# PWM.net
KiCad netlist of a schematic drawn in Altium Designer
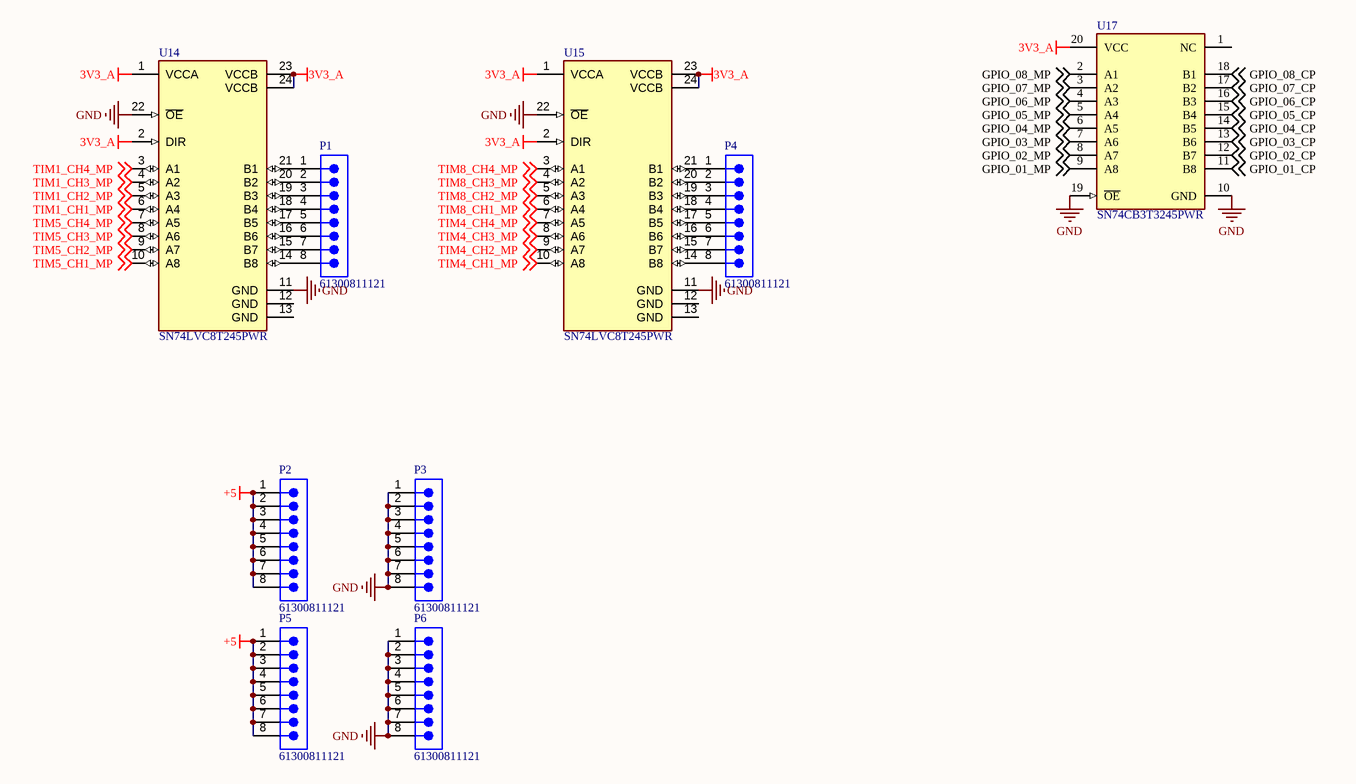
[diagram p0: PWM.SchDoc]

(export (version "E")
  (design (tool "Eeschema 10.0.6"))
  (components
    (comp (ref "P1")
      (value "61300811121")
      (footprint "61300811121")
      (libsource (lib "Altium Content Vault") (part "Header_Male_1R_08P"))
    )
    (comp (ref "P2")
      (value "61300811121")
      (footprint "61300811121")
      (libsource (lib "Altium Content Vault") (part "Header_Male_1R_08P"))
    )
    (comp (ref "P3")
      (value "61300811121")
      (footprint "61300811121")
      (libsource (lib "Altium Content Vault") (part "Header_Male_1R_08P"))
    )
    (comp (ref "P4")
      (value "61300811121")
      (footprint "61300811121")
      (libsource (lib "Altium Content Vault") (part "Header_Male_1R_08P"))
    )
    (comp (ref "P5")
      (value "61300811121")
      (footprint "61300811121")
      (libsource (lib "Altium Content Vault") (part "Header_Male_1R_08P"))
    )
    (comp (ref "P6")
      (value "61300811121")
      (footprint "61300811121")
      (libsource (lib "Altium Content Vault") (part "Header_Male_1R_08P"))
    )
    (comp (ref "U14")
      (value "SN74LVC8T245PWR")
      (footprint "FP-PW0024A-MFG")
      (description "IC TRNSLTR BIDIRECTIONAL 24TSSOP")
      (fields
        (field (name "OCTOPART") "https://octopart.com/sn74lvc8t245pwr-texas+instruments-517164")
        (field (name "MANUFACTURER") "Texas Instruments")
      )
      (libsource (lib "Altium Content Vault") (part "51221a7e4c45eff2cf920f7ccaf63e0"))
    )
    (comp (ref "U15")
      (value "SN74LVC8T245PWR")
      (footprint "FP-PW0024A-MFG")
      (description "IC TRNSLTR BIDIRECTIONAL 24TSSOP")
      (fields
        (field (name "OCTOPART") "https://octopart.com/sn74lvc8t245pwr-texas+instruments-517164")
        (field (name "MANUFACTURER") "Texas Instruments")
      )
      (libsource (lib "Altium Content Vault") (part "51221a7e4c45eff2cf920f7ccaf63e0"))
    )
    (comp (ref "U17")
      (value "SN74CB3T3245PWR")
      (footprint "FP-PW0020A-MFG")
      (description "IC 2.5/3.3V FET BUS SW 20-TSSOP")
      (libsource (lib "Altium Content Vault") (part "98be695b3fbfc448da199ccefa430d5"))
    )
  )
  (nets
    (net (code "1") (name "+5") (class "Default")
      (node (ref "P2") (pin "1") (pinfunction "1_1") (pintype "passive"))
      (node (ref "P2") (pin "2") (pinfunction "2_2") (pintype "passive"))
      (node (ref "P2") (pin "3") (pinfunction "3_3") (pintype "passive"))
      (node (ref "P2") (pin "4") (pinfunction "4_4") (pintype "passive"))
      (node (ref "P2") (pin "5") (pinfunction "5_5") (pintype "passive"))
      (node (ref "P2") (pin "6") (pinfunction "6_6") (pintype "passive"))
      (node (ref "P2") (pin "7") (pinfunction "7_7") (pintype "passive"))
      (node (ref "P2") (pin "8") (pinfunction "8_8") (pintype "passive"))
      (node (ref "P5") (pin "1") (pinfunction "1_1") (pintype "passive"))
      (node (ref "P5") (pin "2") (pinfunction "2_2") (pintype "passive"))
      (node (ref "P5") (pin "3") (pinfunction "3_3") (pintype "passive"))
      (node (ref "P5") (pin "4") (pinfunction "4_4") (pintype "passive"))
      (node (ref "P5") (pin "5") (pinfunction "5_5") (pintype "passive"))
      (node (ref "P5") (pin "6") (pinfunction "6_6") (pintype "passive"))
      (node (ref "P5") (pin "7") (pinfunction "7_7") (pintype "passive"))
      (node (ref "P5") (pin "8") (pinfunction "8_8") (pintype "passive"))
    )
    (net (code "2") (name "3V3_A") (class "Default")
      (node (ref "U14") (pin "1") (pinfunction "VCCA_1") (pintype "power_in"))
      (node (ref "U14") (pin "2") (pinfunction "DIR_2") (pintype "input"))
      (node (ref "U14") (pin "23") (pinfunction "VCCB_23") (pintype "power_in"))
      (node (ref "U14") (pin "24") (pinfunction "VCCB_24") (pintype "power_in"))
      (node (ref "U15") (pin "1") (pinfunction "VCCA_1") (pintype "power_in"))
      (node (ref "U15") (pin "2") (pinfunction "DIR_2") (pintype "input"))
      (node (ref "U15") (pin "23") (pinfunction "VCCB_23") (pintype "power_in"))
      (node (ref "U15") (pin "24") (pinfunction "VCCB_24") (pintype "power_in"))
      (node (ref "U17") (pin "20") (pinfunction "VCC_20") (pintype "power_in"))
    )
    (net (code "3") (name "GND") (class "Default")
      (node (ref "P3") (pin "1") (pinfunction "1_1") (pintype "passive"))
      (node (ref "P3") (pin "2") (pinfunction "2_2") (pintype "passive"))
      (node (ref "P3") (pin "3") (pinfunction "3_3") (pintype "passive"))
      (node (ref "P3") (pin "4") (pinfunction "4_4") (pintype "passive"))
      (node (ref "P3") (pin "5") (pinfunction "5_5") (pintype "passive"))
      (node (ref "P3") (pin "6") (pinfunction "6_6") (pintype "passive"))
      (node (ref "P3") (pin "7") (pinfunction "7_7") (pintype "passive"))
      (node (ref "P3") (pin "8") (pinfunction "8_8") (pintype "passive"))
      (node (ref "P6") (pin "1") (pinfunction "1_1") (pintype "passive"))
      (node (ref "P6") (pin "2") (pinfunction "2_2") (pintype "passive"))
      (node (ref "P6") (pin "3") (pinfunction "3_3") (pintype "passive"))
      (node (ref "P6") (pin "4") (pinfunction "4_4") (pintype "passive"))
      (node (ref "P6") (pin "5") (pinfunction "5_5") (pintype "passive"))
      (node (ref "P6") (pin "6") (pinfunction "6_6") (pintype "passive"))
      (node (ref "P6") (pin "7") (pinfunction "7_7") (pintype "passive"))
      (node (ref "P6") (pin "8") (pinfunction "8_8") (pintype "passive"))
      (node (ref "U14") (pin "11") (pinfunction "GND_11") (pintype "power_in"))
      (node (ref "U14") (pin "22") (pinfunction "~{OE}_22") (pintype "input"))
      (node (ref "U15") (pin "11") (pinfunction "GND_11") (pintype "power_in"))
      (node (ref "U15") (pin "22") (pinfunction "~{OE}_22") (pintype "input"))
      (node (ref "U17") (pin "10") (pinfunction "GND_10") (pintype "power_in"))
      (node (ref "U17") (pin "19") (pinfunction "~{OE}_19") (pintype "input"))
    )
    (net (code "4") (name "GPIO_01_CP") (class "Default")
      (node (ref "U17") (pin "11") (pinfunction "B8_11") (pintype "passive"))
    )
    (net (code "5") (name "GPIO_01_MP") (class "Default")
      (node (ref "U17") (pin "9") (pinfunction "A8_9") (pintype "passive"))
    )
    (net (code "6") (name "GPIO_02_CP") (class "Default")
      (node (ref "U17") (pin "12") (pinfunction "B7_12") (pintype "passive"))
    )
    (net (code "7") (name "GPIO_02_MP") (class "Default")
      (node (ref "U17") (pin "8") (pinfunction "A7_8") (pintype "passive"))
    )
    (net (code "8") (name "GPIO_03_CP") (class "Default")
      (node (ref "U17") (pin "13") (pinfunction "B6_13") (pintype "passive"))
    )
    (net (code "9") (name "GPIO_03_MP") (class "Default")
      (node (ref "U17") (pin "7") (pinfunction "A6_7") (pintype "passive"))
    )
    (net (code "10") (name "GPIO_04_CP") (class "Default")
      (node (ref "U17") (pin "14") (pinfunction "B5_14") (pintype "passive"))
    )
    (net (code "11") (name "GPIO_04_MP") (class "Default")
      (node (ref "U17") (pin "6") (pinfunction "A5_6") (pintype "passive"))
    )
    (net (code "12") (name "GPIO_05_CP") (class "Default")
      (node (ref "U17") (pin "15") (pinfunction "B4_15") (pintype "passive"))
    )
    (net (code "13") (name "GPIO_05_MP") (class "Default")
      (node (ref "U17") (pin "5") (pinfunction "A4_5") (pintype "passive"))
    )
    (net (code "14") (name "GPIO_06_CP") (class "Default")
      (node (ref "U17") (pin "16") (pinfunction "B3_16") (pintype "passive"))
    )
    (net (code "15") (name "GPIO_06_MP") (class "Default")
      (node (ref "U17") (pin "4") (pinfunction "A3_4") (pintype "passive"))
    )
    (net (code "16") (name "GPIO_07_CP") (class "Default")
      (node (ref "U17") (pin "17") (pinfunction "B2_17") (pintype "passive"))
    )
    (net (code "17") (name "GPIO_07_MP") (class "Default")
      (node (ref "U17") (pin "3") (pinfunction "A2_3") (pintype "passive"))
    )
    (net (code "18") (name "GPIO_08_CP") (class "Default")
      (node (ref "U17") (pin "18") (pinfunction "B1_18") (pintype "passive"))
    )
    (net (code "19") (name "GPIO_08_MP") (class "Default")
      (node (ref "U17") (pin "2") (pinfunction "A1_2") (pintype "passive"))
    )
    (net (code "20") (name "Net-(U14-B1)") (class "Default")
      (node (ref "P1") (pin "1") (pinfunction "1_1") (pintype "passive"))
      (node (ref "U14") (pin "21") (pinfunction "B1_21") (pintype "bidirectional"))
    )
    (net (code "21") (name "Net-(U14-B2)") (class "Default")
      (node (ref "P1") (pin "2") (pinfunction "2_2") (pintype "passive"))
      (node (ref "U14") (pin "20") (pinfunction "B2_20") (pintype "bidirectional"))
    )
    (net (code "22") (name "Net-(U14-B3)") (class "Default")
      (node (ref "P1") (pin "3") (pinfunction "3_3") (pintype "passive"))
      (node (ref "U14") (pin "19") (pinfunction "B3_19") (pintype "bidirectional"))
    )
    (net (code "23") (name "Net-(U14-B4)") (class "Default")
      (node (ref "P1") (pin "4") (pinfunction "4_4") (pintype "passive"))
      (node (ref "U14") (pin "18") (pinfunction "B4_18") (pintype "bidirectional"))
    )
    (net (code "24") (name "Net-(U14-B5)") (class "Default")
      (node (ref "P1") (pin "5") (pinfunction "5_5") (pintype "passive"))
      (node (ref "U14") (pin "17") (pinfunction "B5_17") (pintype "bidirectional"))
    )
    (net (code "25") (name "Net-(U14-B6)") (class "Default")
      (node (ref "P1") (pin "6") (pinfunction "6_6") (pintype "passive"))
      (node (ref "U14") (pin "16") (pinfunction "B6_16") (pintype "bidirectional"))
    )
    (net (code "26") (name "Net-(U14-B7)") (class "Default")
      (node (ref "P1") (pin "7") (pinfunction "7_7") (pintype "passive"))
      (node (ref "U14") (pin "15") (pinfunction "B7_15") (pintype "bidirectional"))
    )
    (net (code "27") (name "Net-(U14-B8)") (class "Default")
      (node (ref "P1") (pin "8") (pinfunction "8_8") (pintype "passive"))
      (node (ref "U14") (pin "14") (pinfunction "B8_14") (pintype "bidirectional"))
    )
    (net (code "28") (name "Net-(U15-B1)") (class "Default")
      (node (ref "P4") (pin "1") (pinfunction "1_1") (pintype "passive"))
      (node (ref "U15") (pin "21") (pinfunction "B1_21") (pintype "bidirectional"))
    )
    (net (code "29") (name "Net-(U15-B2)") (class "Default")
      (node (ref "P4") (pin "2") (pinfunction "2_2") (pintype "passive"))
      (node (ref "U15") (pin "20") (pinfunction "B2_20") (pintype "bidirectional"))
    )
    (net (code "30") (name "Net-(U15-B3)") (class "Default")
      (node (ref "P4") (pin "3") (pinfunction "3_3") (pintype "passive"))
      (node (ref "U15") (pin "19") (pinfunction "B3_19") (pintype "bidirectional"))
    )
    (net (code "31") (name "Net-(U15-B4)") (class "Default")
      (node (ref "P4") (pin "4") (pinfunction "4_4") (pintype "passive"))
      (node (ref "U15") (pin "18") (pinfunction "B4_18") (pintype "bidirectional"))
    )
    (net (code "32") (name "Net-(U15-B5)") (class "Default")
      (node (ref "P4") (pin "5") (pinfunction "5_5") (pintype "passive"))
      (node (ref "U15") (pin "17") (pinfunction "B5_17") (pintype "bidirectional"))
    )
    (net (code "33") (name "Net-(U15-B6)") (class "Default")
      (node (ref "P4") (pin "6") (pinfunction "6_6") (pintype "passive"))
      (node (ref "U15") (pin "16") (pinfunction "B6_16") (pintype "bidirectional"))
    )
    (net (code "34") (name "Net-(U15-B7)") (class "Default")
      (node (ref "P4") (pin "7") (pinfunction "7_7") (pintype "passive"))
      (node (ref "U15") (pin "15") (pinfunction "B7_15") (pintype "bidirectional"))
    )
    (net (code "35") (name "Net-(U15-B8)") (class "Default")
      (node (ref "P4") (pin "8") (pinfunction "8_8") (pintype "passive"))
      (node (ref "U15") (pin "14") (pinfunction "B8_14") (pintype "bidirectional"))
    )
    (net (code "36") (name "TIM1_CH1_MP") (class "Default")
      (node (ref "U14") (pin "6") (pinfunction "A4_6") (pintype "bidirectional"))
    )
    (net (code "37") (name "TIM1_CH2_MP") (class "Default")
      (node (ref "U14") (pin "5") (pinfunction "A3_5") (pintype "bidirectional"))
    )
    (net (code "38") (name "TIM1_CH3_MP") (class "Default")
      (node (ref "U14") (pin "4") (pinfunction "A2_4") (pintype "bidirectional"))
    )
    (net (code "39") (name "TIM1_CH4_MP") (class "Default")
      (node (ref "U14") (pin "3") (pinfunction "A1_3") (pintype "bidirectional"))
    )
    (net (code "40") (name "TIM4_CH1_MP") (class "Default")
      (node (ref "U15") (pin "10") (pinfunction "A8_10") (pintype "bidirectional"))
    )
    (net (code "41") (name "TIM4_CH2_MP") (class "Default")
      (node (ref "U15") (pin "9") (pinfunction "A7_9") (pintype "bidirectional"))
    )
    (net (code "42") (name "TIM4_CH3_MP") (class "Default")
      (node (ref "U15") (pin "8") (pinfunction "A6_8") (pintype "bidirectional"))
    )
    (net (code "43") (name "TIM4_CH4_MP") (class "Default")
      (node (ref "U15") (pin "7") (pinfunction "A5_7") (pintype "bidirectional"))
    )
    (net (code "44") (name "TIM5_CH1_MP") (class "Default")
      (node (ref "U14") (pin "10") (pinfunction "A8_10") (pintype "bidirectional"))
    )
    (net (code "45") (name "TIM5_CH2_MP") (class "Default")
      (node (ref "U14") (pin "9") (pinfunction "A7_9") (pintype "bidirectional"))
    )
    (net (code "46") (name "TIM5_CH3_MP") (class "Default")
      (node (ref "U14") (pin "8") (pinfunction "A6_8") (pintype "bidirectional"))
    )
    (net (code "47") (name "TIM5_CH4_MP") (class "Default")
      (node (ref "U14") (pin "7") (pinfunction "A5_7") (pintype "bidirectional"))
    )
    (net (code "48") (name "TIM8_CH1_MP") (class "Default")
      (node (ref "U15") (pin "6") (pinfunction "A4_6") (pintype "bidirectional"))
    )
    (net (code "49") (name "TIM8_CH2_MP") (class "Default")
      (node (ref "U15") (pin "5") (pinfunction "A3_5") (pintype "bidirectional"))
    )
    (net (code "50") (name "TIM8_CH3_MP") (class "Default")
      (node (ref "U15") (pin "4") (pinfunction "A2_4") (pintype "bidirectional"))
    )
    (net (code "51") (name "TIM8_CH4_MP") (class "Default")
      (node (ref "U15") (pin "3") (pinfunction "A1_3") (pintype "bidirectional"))
    )
    (net (code "52") (name "unconnected-(U14-GND-Pad12)") (class "Default")
      (node (ref "U14") (pin "12") (pinfunction "GND_12") (pintype "power_in"))
    )
    (net (code "53") (name "unconnected-(U14-GND-Pad13)") (class "Default")
      (node (ref "U14") (pin "13") (pinfunction "GND_13") (pintype "power_in"))
    )
    (net (code "54") (name "unconnected-(U15-GND-Pad12)") (class "Default")
      (node (ref "U15") (pin "12") (pinfunction "GND_12") (pintype "power_in"))
    )
    (net (code "55") (name "unconnected-(U15-GND-Pad13)") (class "Default")
      (node (ref "U15") (pin "13") (pinfunction "GND_13") (pintype "power_in"))
    )
    (net (code "56") (name "unconnected-(U17-NC-Pad1)") (class "Default")
      (node (ref "U17") (pin "1") (pinfunction "NC_1") (pintype "passive"))
    )
  )
)
